# Power_Distribution_-_Spare_Outputs.net
KiCad netlist of a schematic drawn in Altium Designer
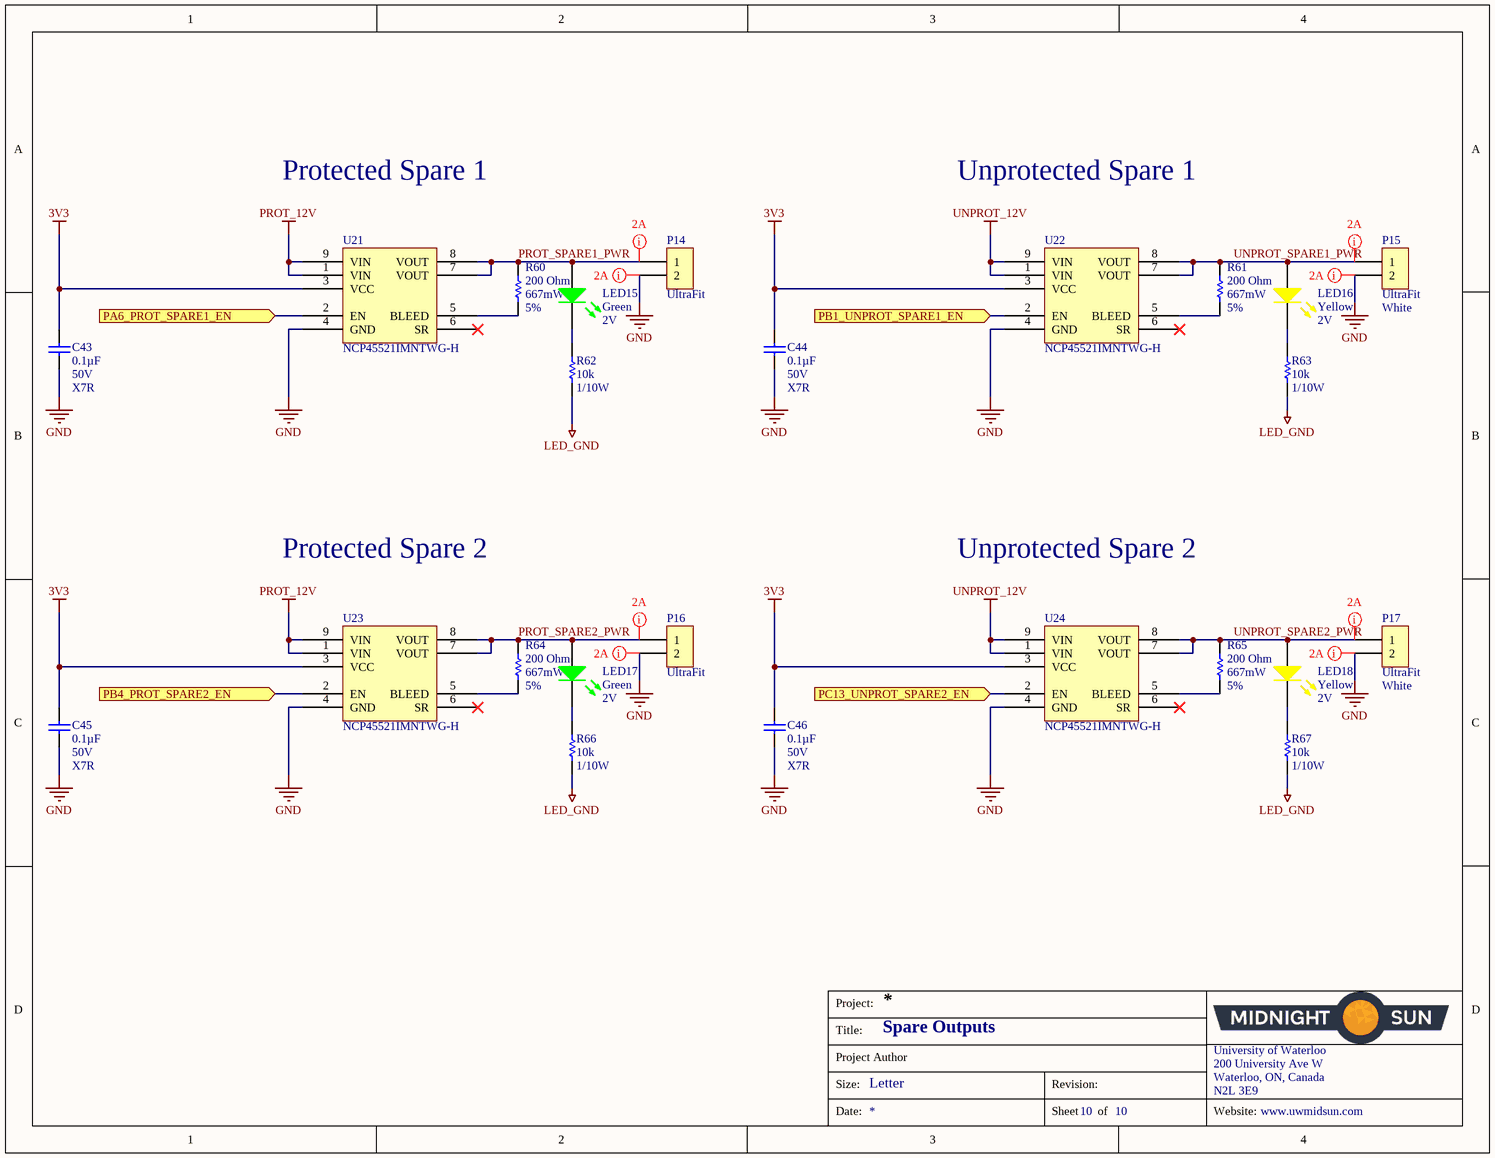
[diagram p0: Power Distribution - Spare Outputs.SchDoc]

(export (version "E")
  (design (tool "Eeschema 10.0.6"))
  (components
    (comp (ref "C43")
      (value "CAP CER 0.1UF 50V 10% X7R 0603")
      (footprint "CAP, 0603")
      (description "0.10µF ±10% 50V Ceramic Capacitor X7R 0603 (1608 Metric)")
      (fields
        (field (name "TOLERANCE") "±10%")
        (field (name "CAPACITANCE") "0.1µF")
        (field (name "VOLTAGE") "50V")
        (field (name "TEMPERATURE COEFFICIENT") "X7R")
      )
      (libsource (lib "Schematic Diagrams") (part "CAP CER 0.1UF 50V 10% X7R 0603"))
    )
    (comp (ref "C44")
      (value "CAP CER 0.1UF 50V 10% X7R 0603")
      (footprint "CAP, 0603")
      (description "0.10µF ±10% 50V Ceramic Capacitor X7R 0603 (1608 Metric)")
      (fields
        (field (name "TOLERANCE") "±10%")
        (field (name "CAPACITANCE") "0.1µF")
        (field (name "VOLTAGE") "50V")
        (field (name "TEMPERATURE COEFFICIENT") "X7R")
      )
      (libsource (lib "Schematic Diagrams") (part "CAP CER 0.1UF 50V 10% X7R 0603"))
    )
    (comp (ref "C45")
      (value "CAP CER 0.1UF 50V 10% X7R 0603")
      (footprint "CAP, 0603")
      (description "0.10µF ±10% 50V Ceramic Capacitor X7R 0603 (1608 Metric)")
      (fields
        (field (name "TOLERANCE") "±10%")
        (field (name "CAPACITANCE") "0.1µF")
        (field (name "VOLTAGE") "50V")
        (field (name "TEMPERATURE COEFFICIENT") "X7R")
      )
      (libsource (lib "Schematic Diagrams") (part "CAP CER 0.1UF 50V 10% X7R 0603"))
    )
    (comp (ref "C46")
      (value "CAP CER 0.1UF 50V 10% X7R 0603")
      (footprint "CAP, 0603")
      (description "0.10µF ±10% 50V Ceramic Capacitor X7R 0603 (1608 Metric)")
      (fields
        (field (name "TOLERANCE") "±10%")
        (field (name "CAPACITANCE") "0.1µF")
        (field (name "VOLTAGE") "50V")
        (field (name "TEMPERATURE COEFFICIENT") "X7R")
      )
      (libsource (lib "Schematic Diagrams") (part "CAP CER 0.1UF 50V 10% X7R 0603"))
    )
    (comp (ref "LED15")
      (value "LED GREEN CLEAR 2V 0603")
      (footprint "LED_0603")
      (description "Green 572nm LED Indication - Discrete 2V 0603 (1608 Metric)")
      (fields
        (field (name "MANUFACTURER") "Wurth Electronics Inc.")
        (field (name "MANUFACTURER PART NUMBER") "150060VS75000")
        (field (name "COLOR") "Green")
        (field (name "VOLTAGE - FORWARD (VF) (TYP)") "2V")
      )
      (libsource (lib "Schematic Diagrams") (part "LED GREEN CLEAR 2V 0603"))
    )
    (comp (ref "LED16")
      (value "LED YELLOW CLEAR 2.1V 0603")
      (footprint "LED_0603")
      (description "Yellow 590nm LED Indication - Discrete 2V 0603 (1608 Metric)")
      (fields
        (field (name "MANUFACTURER") "Wurth Electronics Inc.")
        (field (name "MANUFACTURER PART NUMBER") "150060YS75000")
        (field (name "COLOR") "Yellow")
        (field (name "VOLTAGE - FORWARD (VF) (TYP)") "2V")
      )
      (libsource (lib "Schematic Diagrams") (part "LED YELLOW CLEAR 2.1V 0603"))
    )
    (comp (ref "LED17")
      (value "LED GREEN CLEAR 2V 0603")
      (footprint "LED_0603")
      (description "Green 572nm LED Indication - Discrete 2V 0603 (1608 Metric)")
      (fields
        (field (name "MANUFACTURER") "Wurth Electronics Inc.")
        (field (name "MANUFACTURER PART NUMBER") "150060VS75000")
        (field (name "COLOR") "Green")
        (field (name "VOLTAGE - FORWARD (VF) (TYP)") "2V")
      )
      (libsource (lib "Schematic Diagrams") (part "LED GREEN CLEAR 2V 0603"))
    )
    (comp (ref "LED18")
      (value "LED YELLOW CLEAR 2.1V 0603")
      (footprint "LED_0603")
      (description "Yellow 590nm LED Indication - Discrete 2V 0603 (1608 Metric)")
      (fields
        (field (name "MANUFACTURER") "Wurth Electronics Inc.")
        (field (name "MANUFACTURER PART NUMBER") "150060YS75000")
        (field (name "COLOR") "Yellow")
        (field (name "VOLTAGE - FORWARD (VF) (TYP)") "2V")
      )
      (libsource (lib "Schematic Diagrams") (part "LED YELLOW CLEAR 2.1V 0603"))
    )
    (comp (ref "P14")
      (value "CONN 2POS ULTRA-FIT 0.138\"")
      (footprint "CONN, 2POS ULTRA-FIT")
      (description "2 Positions Header, Shrouded Connector 0.138\" (3.50mm) Through Hole Gold")
      (fields (field (name "VOLTAGE") "400V") (field (name "SERIES") "UltraFit"))
      (libsource (lib "Schematic Diagrams") (part "CONN 2POS ULTRA-FIT 0.138{dblquote}"))
    )
    (comp (ref "P15")
      (value "CONN 2POS ULTRA-FIT NATURAL COLOR 0.138\"")
      (footprint "CONN, 2POS ULTRA-FIT - NATURAL COLOR")
      (description "2 Positions Header, Shrouded Connector 0.138\" (3.50mm) Through Hole")
      (fields
        (field (name "VOLTAGE") "400V")
        (field (name "SERIES") "UltraFit")
        (field (name "COLOR") "White")
      )
      (libsource (lib "Schematic Diagrams") (part "CONN 2POS ULTRA-FIT NATURAL COLOR 0.138{dblquote}"))
    )
    (comp (ref "P16")
      (value "CONN 2POS ULTRA-FIT 0.138\"")
      (footprint "CONN, 2POS ULTRA-FIT")
      (description "2 Positions Header, Shrouded Connector 0.138\" (3.50mm) Through Hole Gold")
      (fields (field (name "VOLTAGE") "400V") (field (name "SERIES") "UltraFit"))
      (libsource (lib "Schematic Diagrams") (part "CONN 2POS ULTRA-FIT 0.138{dblquote}"))
    )
    (comp (ref "P17")
      (value "CONN 2POS ULTRA-FIT NATURAL COLOR 0.138\"")
      (footprint "CONN, 2POS ULTRA-FIT - NATURAL COLOR")
      (description "2 Positions Header, Shrouded Connector 0.138\" (3.50mm) Through Hole")
      (fields
        (field (name "VOLTAGE") "400V")
        (field (name "SERIES") "UltraFit")
        (field (name "COLOR") "White")
      )
      (libsource (lib "Schematic Diagrams") (part "CONN 2POS ULTRA-FIT NATURAL COLOR 0.138{dblquote}"))
    )
    (comp (ref "R60")
      (value "200 Ohm")
      (footprint "RES 1206")
      (fields
        (field (name "MANUFACTURER") "Panasonic")
        (field (name "MANUFACTURER PART NUMBER") "ERJ-P08J201V")
        (field (name "TOLERANCE") "5%")
        (field (name "MAX POWER DISSIPATION") "667mW")
      )
      (libsource (lib "Schematic Diagrams") (part "RES 200 OHM 5% 2/3W 1206"))
    )
    (comp (ref "R61")
      (value "200 Ohm")
      (footprint "RES 1206")
      (fields
        (field (name "MANUFACTURER") "Panasonic")
        (field (name "MANUFACTURER PART NUMBER") "ERJ-P08J201V")
        (field (name "TOLERANCE") "5%")
        (field (name "MAX POWER DISSIPATION") "667mW")
      )
      (libsource (lib "Schematic Diagrams") (part "RES 200 OHM 5% 2/3W 1206"))
    )
    (comp (ref "R62")
      (value "RES 10K OHM 1% 1/10W 0603")
      (footprint "RES, 0603")
      (description "RES SMD 10K OHM 1% 1/10W 0603")
      (fields
        (field (name "TOLERANCE") "±1%")
        (field (name "RESISTANCE") "10k")
        (field (name "POWER") "1/10W")
      )
      (libsource (lib "Schematic Diagrams") (part "RES 10K OHM 1% 1/10W 0603"))
    )
    (comp (ref "R63")
      (value "RES 10K OHM 1% 1/10W 0603")
      (footprint "RES, 0603")
      (description "RES SMD 10K OHM 1% 1/10W 0603")
      (fields
        (field (name "TOLERANCE") "±1%")
        (field (name "RESISTANCE") "10k")
        (field (name "POWER") "1/10W")
      )
      (libsource (lib "Schematic Diagrams") (part "RES 10K OHM 1% 1/10W 0603"))
    )
    (comp (ref "R64")
      (value "200 Ohm")
      (footprint "RES 1206")
      (fields
        (field (name "MANUFACTURER") "Panasonic")
        (field (name "MANUFACTURER PART NUMBER") "ERJ-P08J201V")
        (field (name "TOLERANCE") "5%")
        (field (name "MAX POWER DISSIPATION") "667mW")
      )
      (libsource (lib "Schematic Diagrams") (part "RES 200 OHM 5% 2/3W 1206"))
    )
    (comp (ref "R65")
      (value "200 Ohm")
      (footprint "RES 1206")
      (fields
        (field (name "MANUFACTURER") "Panasonic")
        (field (name "MANUFACTURER PART NUMBER") "ERJ-P08J201V")
        (field (name "TOLERANCE") "5%")
        (field (name "MAX POWER DISSIPATION") "667mW")
      )
      (libsource (lib "Schematic Diagrams") (part "RES 200 OHM 5% 2/3W 1206"))
    )
    (comp (ref "R66")
      (value "RES 10K OHM 1% 1/10W 0603")
      (footprint "RES, 0603")
      (description "RES SMD 10K OHM 1% 1/10W 0603")
      (fields
        (field (name "TOLERANCE") "±1%")
        (field (name "RESISTANCE") "10k")
        (field (name "POWER") "1/10W")
      )
      (libsource (lib "Schematic Diagrams") (part "RES 10K OHM 1% 1/10W 0603"))
    )
    (comp (ref "R67")
      (value "RES 10K OHM 1% 1/10W 0603")
      (footprint "RES, 0603")
      (description "RES SMD 10K OHM 1% 1/10W 0603")
      (fields
        (field (name "TOLERANCE") "±1%")
        (field (name "RESISTANCE") "10k")
        (field (name "POWER") "1/10W")
      )
      (libsource (lib "Schematic Diagrams") (part "RES 10K OHM 1% 1/10W 0603"))
    )
    (comp (ref "U21")
      (value "IC LOAD SWITCH ACT-HI 10.5A 8DFN")
      (footprint "IC LOAD SWITCH ACT-HI 10.5A 8DFN")
      (description "NCP45521IMNTWG-H")
      (fields
        (field (name "MANUFACTURER") "ON Semiconductor")
        (field (name "MANUFACTURER PART NUMBER") "NCP45521IMNTWG-H")
      )
      (libsource (lib "Schematic Diagrams") (part "IC LOAD SWITCH ACT-HI 10.5A 8DFN"))
    )
    (comp (ref "U22")
      (value "IC LOAD SWITCH ACT-HI 10.5A 8DFN")
      (footprint "IC LOAD SWITCH ACT-HI 10.5A 8DFN")
      (description "NCP45521IMNTWG-H")
      (fields
        (field (name "MANUFACTURER") "ON Semiconductor")
        (field (name "MANUFACTURER PART NUMBER") "NCP45521IMNTWG-H")
      )
      (libsource (lib "Schematic Diagrams") (part "IC LOAD SWITCH ACT-HI 10.5A 8DFN"))
    )
    (comp (ref "U23")
      (value "IC LOAD SWITCH ACT-HI 10.5A 8DFN")
      (footprint "IC LOAD SWITCH ACT-HI 10.5A 8DFN")
      (description "NCP45521IMNTWG-H")
      (fields
        (field (name "MANUFACTURER") "ON Semiconductor")
        (field (name "MANUFACTURER PART NUMBER") "NCP45521IMNTWG-H")
      )
      (libsource (lib "Schematic Diagrams") (part "IC LOAD SWITCH ACT-HI 10.5A 8DFN"))
    )
    (comp (ref "U24")
      (value "IC LOAD SWITCH ACT-HI 10.5A 8DFN")
      (footprint "IC LOAD SWITCH ACT-HI 10.5A 8DFN")
      (description "NCP45521IMNTWG-H")
      (fields
        (field (name "MANUFACTURER") "ON Semiconductor")
        (field (name "MANUFACTURER PART NUMBER") "NCP45521IMNTWG-H")
      )
      (libsource (lib "Schematic Diagrams") (part "IC LOAD SWITCH ACT-HI 10.5A 8DFN"))
    )
  )
  (nets
    (net (code "1") (name "/PA6_PROT_SPARE1_EN") (class "Default")
      (node (ref "U21") (pin "2") (pinfunction "EN_2") (pintype "passive"))
    )
    (net (code "2") (name "/PB1_UNPROT_SPARE1_EN") (class "Default")
      (node (ref "U22") (pin "2") (pinfunction "EN_2") (pintype "passive"))
    )
    (net (code "3") (name "/PB4_PROT_SPARE2_EN") (class "Default")
      (node (ref "U23") (pin "2") (pinfunction "EN_2") (pintype "passive"))
    )
    (net (code "4") (name "/PC13_UNPROT_SPARE2_EN") (class "Default")
      (node (ref "U24") (pin "2") (pinfunction "EN_2") (pintype "passive"))
    )
    (net (code "5") (name "/PROT_SPARE1_PWR") (class "Default")
      (node (ref "LED15") (pin "1") (pinfunction "A_1") (pintype "passive"))
      (node (ref "P14") (pin "1") (pinfunction "1_1") (pintype "passive"))
      (node (ref "R60") (pin "1") (pinfunction "1_1") (pintype "passive"))
      (node (ref "U21") (pin "7") (pinfunction "VOUT_7") (pintype "passive"))
      (node (ref "U21") (pin "8") (pinfunction "VOUT_8") (pintype "passive"))
    )
    (net (code "6") (name "/PROT_SPARE2_PWR") (class "Default")
      (node (ref "LED17") (pin "1") (pinfunction "A_1") (pintype "passive"))
      (node (ref "P16") (pin "1") (pinfunction "1_1") (pintype "passive"))
      (node (ref "R64") (pin "1") (pinfunction "1_1") (pintype "passive"))
      (node (ref "U23") (pin "7") (pinfunction "VOUT_7") (pintype "passive"))
      (node (ref "U23") (pin "8") (pinfunction "VOUT_8") (pintype "passive"))
    )
    (net (code "7") (name "/UNPROT_SPARE1_PWR") (class "Default")
      (node (ref "LED16") (pin "1") (pinfunction "A_1") (pintype "passive"))
      (node (ref "P15") (pin "1") (pinfunction "1_1") (pintype "passive"))
      (node (ref "R61") (pin "1") (pinfunction "1_1") (pintype "passive"))
      (node (ref "U22") (pin "7") (pinfunction "VOUT_7") (pintype "passive"))
      (node (ref "U22") (pin "8") (pinfunction "VOUT_8") (pintype "passive"))
    )
    (net (code "8") (name "/UNPROT_SPARE2_PWR") (class "Default")
      (node (ref "LED18") (pin "1") (pinfunction "A_1") (pintype "passive"))
      (node (ref "P17") (pin "1") (pinfunction "1_1") (pintype "passive"))
      (node (ref "R65") (pin "1") (pinfunction "1_1") (pintype "passive"))
      (node (ref "U24") (pin "7") (pinfunction "VOUT_7") (pintype "passive"))
      (node (ref "U24") (pin "8") (pinfunction "VOUT_8") (pintype "passive"))
    )
    (net (code "9") (name "3V3") (class "Default")
      (node (ref "C43") (pin "1") (pinfunction "1_1") (pintype "passive"))
      (node (ref "C44") (pin "1") (pinfunction "1_1") (pintype "passive"))
      (node (ref "C45") (pin "1") (pinfunction "1_1") (pintype "passive"))
      (node (ref "C46") (pin "1") (pinfunction "1_1") (pintype "passive"))
      (node (ref "U21") (pin "3") (pinfunction "VCC_3") (pintype "passive"))
      (node (ref "U22") (pin "3") (pinfunction "VCC_3") (pintype "passive"))
      (node (ref "U23") (pin "3") (pinfunction "VCC_3") (pintype "passive"))
      (node (ref "U24") (pin "3") (pinfunction "VCC_3") (pintype "passive"))
    )
    (net (code "10") (name "GND") (class "Default")
      (node (ref "C43") (pin "2") (pinfunction "2_2") (pintype "passive"))
      (node (ref "C44") (pin "2") (pinfunction "2_2") (pintype "passive"))
      (node (ref "C45") (pin "2") (pinfunction "2_2") (pintype "passive"))
      (node (ref "C46") (pin "2") (pinfunction "2_2") (pintype "passive"))
      (node (ref "P14") (pin "2") (pinfunction "2_2") (pintype "passive"))
      (node (ref "P15") (pin "2") (pinfunction "2_2") (pintype "passive"))
      (node (ref "P16") (pin "2") (pinfunction "2_2") (pintype "passive"))
      (node (ref "P17") (pin "2") (pinfunction "2_2") (pintype "passive"))
      (node (ref "U21") (pin "4") (pinfunction "GND_4") (pintype "passive"))
      (node (ref "U22") (pin "4") (pinfunction "GND_4") (pintype "passive"))
      (node (ref "U23") (pin "4") (pinfunction "GND_4") (pintype "passive"))
      (node (ref "U24") (pin "4") (pinfunction "GND_4") (pintype "passive"))
    )
    (net (code "11") (name "LED_GND") (class "Default")
      (node (ref "R62") (pin "2") (pinfunction "2_2") (pintype "passive"))
      (node (ref "R63") (pin "2") (pinfunction "2_2") (pintype "passive"))
      (node (ref "R66") (pin "2") (pinfunction "2_2") (pintype "passive"))
      (node (ref "R67") (pin "2") (pinfunction "2_2") (pintype "passive"))
    )
    (net (code "12") (name "Net-(LED15-K)") (class "Default")
      (node (ref "LED15") (pin "2") (pinfunction "K_2") (pintype "passive"))
      (node (ref "R62") (pin "1") (pinfunction "1_1") (pintype "passive"))
    )
    (net (code "13") (name "Net-(LED16-K)") (class "Default")
      (node (ref "LED16") (pin "2") (pinfunction "K_2") (pintype "passive"))
      (node (ref "R63") (pin "1") (pinfunction "1_1") (pintype "passive"))
    )
    (net (code "14") (name "Net-(LED17-K)") (class "Default")
      (node (ref "LED17") (pin "2") (pinfunction "K_2") (pintype "passive"))
      (node (ref "R66") (pin "1") (pinfunction "1_1") (pintype "passive"))
    )
    (net (code "15") (name "Net-(LED18-K)") (class "Default")
      (node (ref "LED18") (pin "2") (pinfunction "K_2") (pintype "passive"))
      (node (ref "R67") (pin "1") (pinfunction "1_1") (pintype "passive"))
    )
    (net (code "16") (name "Net-(U21-BLEED)") (class "Default")
      (node (ref "R60") (pin "2") (pinfunction "2_2") (pintype "passive"))
      (node (ref "U21") (pin "5") (pinfunction "BLEED_5") (pintype "passive"))
    )
    (net (code "17") (name "Net-(U22-BLEED)") (class "Default")
      (node (ref "R61") (pin "2") (pinfunction "2_2") (pintype "passive"))
      (node (ref "U22") (pin "5") (pinfunction "BLEED_5") (pintype "passive"))
    )
    (net (code "18") (name "Net-(U23-BLEED)") (class "Default")
      (node (ref "R64") (pin "2") (pinfunction "2_2") (pintype "passive"))
      (node (ref "U23") (pin "5") (pinfunction "BLEED_5") (pintype "passive"))
    )
    (net (code "19") (name "Net-(U24-BLEED)") (class "Default")
      (node (ref "R65") (pin "2") (pinfunction "2_2") (pintype "passive"))
      (node (ref "U24") (pin "5") (pinfunction "BLEED_5") (pintype "passive"))
    )
    (net (code "20") (name "PROT_12V") (class "Default")
      (node (ref "U21") (pin "1") (pinfunction "VIN_1") (pintype "passive"))
      (node (ref "U21") (pin "9") (pinfunction "VIN_9") (pintype "passive"))
      (node (ref "U23") (pin "1") (pinfunction "VIN_1") (pintype "passive"))
      (node (ref "U23") (pin "9") (pinfunction "VIN_9") (pintype "passive"))
    )
    (net (code "21") (name "UNPROT_12V") (class "Default")
      (node (ref "U22") (pin "1") (pinfunction "VIN_1") (pintype "passive"))
      (node (ref "U22") (pin "9") (pinfunction "VIN_9") (pintype "passive"))
      (node (ref "U24") (pin "1") (pinfunction "VIN_1") (pintype "passive"))
      (node (ref "U24") (pin "9") (pinfunction "VIN_9") (pintype "passive"))
    )
    (net (code "22") (name "unconnected-(U21-SR-Pad6)") (class "Default")
      (node (ref "U21") (pin "6") (pinfunction "SR_6") (pintype "passive+no_connect"))
    )
    (net (code "23") (name "unconnected-(U22-SR-Pad6)") (class "Default")
      (node (ref "U22") (pin "6") (pinfunction "SR_6") (pintype "passive+no_connect"))
    )
    (net (code "24") (name "unconnected-(U23-SR-Pad6)") (class "Default")
      (node (ref "U23") (pin "6") (pinfunction "SR_6") (pintype "passive+no_connect"))
    )
    (net (code "25") (name "unconnected-(U24-SR-Pad6)") (class "Default")
      (node (ref "U24") (pin "6") (pinfunction "SR_6") (pintype "passive+no_connect"))
    )
  )
)
